# MainBoard_V100_PEAKDET.net
KiCad netlist of a schematic drawn in Altium Designer
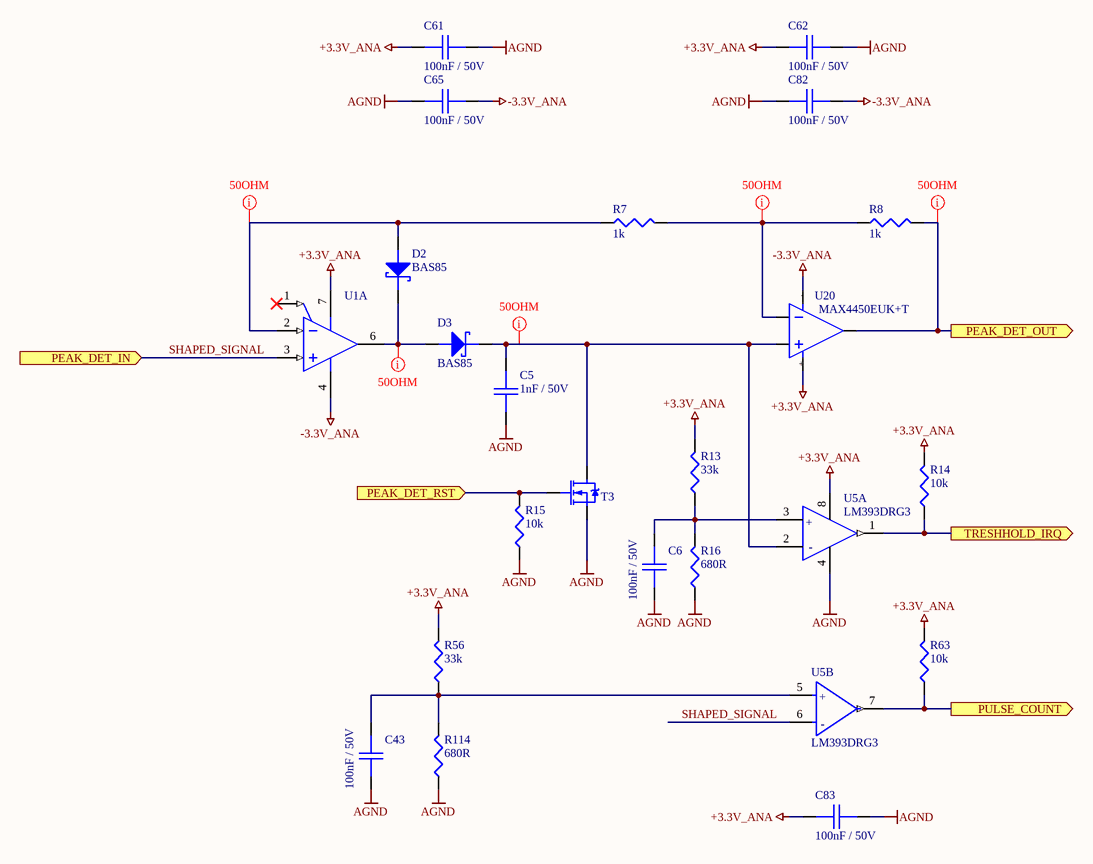
[diagram p0: MainBoard_V100_PEAKDET.SchDoc]

(export (version "E")
  (design (tool "Eeschema 10.0.6"))
  (components
    (comp (ref "C5")
      (value "1nF / 50V")
      (footprint "0805_C")
      (description "1nF 50V X7R")
      (fields (field (name "PART NUMBER") "SMD0805-1nF-50V"))
      (libsource (lib "ALTIUM_DB_LIB") (part "CAP_NONPOL"))
    )
    (comp (ref "C6")
      (value "100nF / 50V")
      (footprint "0805_C")
      (description "100nF 50V X7R")
      (fields (field (name "PART NUMBER") "SMD0805-100nF-50V"))
      (libsource (lib "ALTIUM_DB_LIB") (part "CAP_NONPOL"))
    )
    (comp (ref "C43")
      (value "100nF / 50V")
      (footprint "0805_C")
      (description "100nF 50V X7R")
      (fields (field (name "PART NUMBER") "SMD0805-100nF-50V"))
      (libsource (lib "ALTIUM_DB_LIB") (part "CAP_NONPOL"))
    )
    (comp (ref "C61")
      (value "100nF / 50V")
      (footprint "0805_C")
      (description "100nF 50V X7R")
      (fields (field (name "PART NUMBER") "SMD0805-100nF-50V"))
      (libsource (lib "ALTIUM_DB_LIB") (part "CAP_NONPOL"))
    )
    (comp (ref "C62")
      (value "100nF / 50V")
      (footprint "0805_C")
      (description "100nF 50V X7R")
      (fields (field (name "PART NUMBER") "SMD0805-100nF-50V"))
      (libsource (lib "ALTIUM_DB_LIB") (part "CAP_NONPOL"))
    )
    (comp (ref "C65")
      (value "100nF / 50V")
      (footprint "0805_C")
      (description "100nF 50V X7R")
      (fields (field (name "PART NUMBER") "SMD0805-100nF-50V"))
      (libsource (lib "ALTIUM_DB_LIB") (part "CAP_NONPOL"))
    )
    (comp (ref "C82")
      (value "100nF / 50V")
      (footprint "0805_C")
      (description "100nF 50V X7R")
      (fields (field (name "PART NUMBER") "SMD0805-100nF-50V"))
      (libsource (lib "ALTIUM_DB_LIB") (part "CAP_NONPOL"))
    )
    (comp (ref "C83")
      (value "100nF / 50V")
      (footprint "0805_C")
      (description "100nF 50V X7R")
      (fields (field (name "PART NUMBER") "SMD0805-100nF-50V"))
      (libsource (lib "ALTIUM_DB_LIB") (part "CAP_NONPOL"))
    )
    (comp (ref "D2")
      (value "BAS85")
      (footprint "SOD80")
      (description "Small Signal Schottky Diode, Single, 30 V, 200 mA,  125 °C")
      (libsource (lib "ALTIUM_DB_LIB") (part "DIODE_SCHOTTKY"))
    )
    (comp (ref "D3")
      (value "BAS85")
      (footprint "SOD80")
      (description "Small Signal Schottky Diode, Single, 30 V, 200 mA,  125 °C")
      (libsource (lib "ALTIUM_DB_LIB") (part "DIODE_SCHOTTKY"))
    )
    (comp (ref "R7")
      (value "1k")
      (footprint "0805")
      (description "1k 0805 0.125W 1%")
      (fields (field (name "PART NUMBER") "SMD0805-1k 1%"))
      (libsource (lib "ALTIUM_DB_LIB") (part "RESISTOR"))
    )
    (comp (ref "R8")
      (value "1k")
      (footprint "0805")
      (description "1k 0805 0.125W 1%")
      (fields (field (name "PART NUMBER") "SMD0805-1k 1%"))
      (libsource (lib "ALTIUM_DB_LIB") (part "RESISTOR"))
    )
    (comp (ref "R13")
      (value "33k")
      (footprint "0805")
      (description "33k 0805 0.125W 5%")
      (fields (field (name "PART NUMBER") "SMD0805-33k 5%"))
      (libsource (lib "ALTIUM_DB_LIB") (part "RESISTOR"))
    )
    (comp (ref "R14")
      (value "10k")
      (footprint "0805")
      (description "10k 0805 0.125W 1%")
      (fields (field (name "PART NUMBER") "SMD0805-10k 1%"))
      (libsource (lib "ALTIUM_DB_LIB") (part "RESISTOR"))
    )
    (comp (ref "R15")
      (value "10k")
      (footprint "0805")
      (description "10k 0805 0.125W 1%")
      (fields (field (name "PART NUMBER") "SMD0805-10k 1%"))
      (libsource (lib "ALTIUM_DB_LIB") (part "RESISTOR"))
    )
    (comp (ref "R16")
      (value "680R")
      (footprint "0805")
      (description "680R 0805 0.125W 5%")
      (fields (field (name "PART NUMBER") "SMD0805-680R 5%"))
      (libsource (lib "ALTIUM_DB_LIB") (part "RESISTOR"))
    )
    (comp (ref "R56")
      (value "33k")
      (footprint "0805")
      (description "33k 0805 0.125W 5%")
      (fields (field (name "PART NUMBER") "SMD0805-33k 5%"))
      (libsource (lib "ALTIUM_DB_LIB") (part "RESISTOR"))
    )
    (comp (ref "R63")
      (value "10k")
      (footprint "0805")
      (description "10k 0805 0.125W 1%")
      (fields (field (name "PART NUMBER") "SMD0805-10k 1%"))
      (libsource (lib "ALTIUM_DB_LIB") (part "RESISTOR"))
    )
    (comp (ref "R114")
      (value "680R")
      (footprint "0805")
      (description "680R 0805 0.125W 5%")
      (fields (field (name "PART NUMBER") "SMD0805-680R 5%"))
      (libsource (lib "ALTIUM_DB_LIB") (part "RESISTOR"))
    )
    (comp (ref "T3")
      (value "2N7002K-7")
      (footprint "SOT-23")
      (description "2N7002K-7 Power MOSFET, N Channel, 60 V, 300 mA, 2 ohm, SOT-23, Surface Mount")
      (libsource (lib "ALTIUM_DB_LIB") (part "MOSFET_N_CH"))
    )
    (comp (ref "U1")
      (value "LT1806CS8#PBF")
      (footprint "SO-8")
      (fields
        (field (name "MANUFACTURER") "Linear Technology")
        (field (name "LINEAR TECHNOLOGY PART NUMBER") "LT1806")
      )
      (libsource (lib "ALTIUM_DB_LIB") (part "LT1806CS8#PBF"))
    )
    (comp (ref "U5")
      (value "LM393DRG3")
      (footprint "SO-8")
      (description "IC VOLT COMPARATOR DUAL LP 8SOIC")
      (fields
        (field (name "MANUFACTURER PART NUMBER") "LM393D")
        (field (name "OCTOPART") "https://octopart.com/lm393d-stmicroelectronics-25832")
      )
      (libsource (lib "ALTIUM_DB_LIB") (part "LM393DRG3"))
    )
    (comp (ref "U20")
      (value "MAX4450EUK+T")
      (footprint "SOT-23-5")
      (description "Operational Amplifier, Rail to Rail Output, SOT-23-5, 210 MHz, 485 V/µs")
      (libsource (lib "ALTIUM_DB_LIB") (part "MAX445X"))
    )
  )
  (nets
    (net (code "1") (name "+3.3V_ANA") (class "Default")
      (node (ref "C61") (pin "1") (pintype "passive"))
      (node (ref "C62") (pin "1") (pintype "passive"))
      (node (ref "C83") (pin "1") (pintype "passive"))
      (node (ref "R13") (pin "2") (pintype "passive"))
      (node (ref "R14") (pin "2") (pintype "passive"))
      (node (ref "R56") (pin "2") (pintype "passive"))
      (node (ref "R63") (pin "2") (pintype "passive"))
      (node (ref "U1") (pin "7") (pinfunction "V+_7") (pintype "power_in"))
      (node (ref "U20") (pin "5") (pinfunction "VCC_5") (pintype "passive"))
      (node (ref "U5") (pin "8") (pinfunction "Vcc+_8") (pintype "power_in"))
    )
    (net (code "2") (name "-3.3V_ANA") (class "Default")
      (node (ref "C65") (pin "2") (pintype "passive"))
      (node (ref "C82") (pin "2") (pintype "passive"))
      (node (ref "U1") (pin "4") (pinfunction "V-_4") (pintype "power_in"))
      (node (ref "U20") (pin "4") (pinfunction "GND_4") (pintype "passive"))
    )
    (net (code "3") (name "/PEAK_DET_OUT") (class "Default")
      (node (ref "R8") (pin "2") (pintype "passive"))
      (node (ref "U20") (pin "1") (pinfunction "OUT_1") (pintype "passive"))
    )
    (net (code "4") (name "/PEAK_DET_RST") (class "Default")
      (node (ref "R15") (pin "2") (pintype "passive"))
      (node (ref "T3") (pin "1") (pinfunction "G_1") (pintype "passive"))
    )
    (net (code "5") (name "/PULSE_COUNT") (class "Default")
      (node (ref "R63") (pin "1") (pintype "passive"))
      (node (ref "U5") (pin "7") (pinfunction "Out2_7") (pintype "output"))
    )
    (net (code "6") (name "/SHAPED_SIGNAL") (class "Default")
      (node (ref "U1") (pin "3") (pinfunction "+IN_3") (pintype "input"))
      (node (ref "U5") (pin "6") (pinfunction "In2-_6") (pintype "tri_state"))
    )
    (net (code "7") (name "/TRESHHOLD_IRQ") (class "Default")
      (node (ref "R14") (pin "1") (pintype "passive"))
      (node (ref "U5") (pin "1") (pinfunction "Out1_1") (pintype "output"))
    )
    (net (code "8") (name "AGND") (class "Default")
      (node (ref "C43") (pin "2") (pintype "passive"))
      (node (ref "C5") (pin "2") (pintype "passive"))
      (node (ref "C6") (pin "2") (pintype "passive"))
      (node (ref "C61") (pin "2") (pintype "passive"))
      (node (ref "C62") (pin "2") (pintype "passive"))
      (node (ref "C65") (pin "1") (pintype "passive"))
      (node (ref "C82") (pin "1") (pintype "passive"))
      (node (ref "C83") (pin "2") (pintype "passive"))
      (node (ref "R114") (pin "1") (pintype "passive"))
      (node (ref "R15") (pin "1") (pintype "passive"))
      (node (ref "R16") (pin "1") (pintype "passive"))
      (node (ref "T3") (pin "2") (pinfunction "S_2") (pintype "passive"))
      (node (ref "U5") (pin "4") (pinfunction "Vcc-_4") (pintype "power_in"))
    )
    (net (code "9") (name "Net-(T3-D)") (class "Default")
      (node (ref "C5") (pin "1") (pintype "passive"))
      (node (ref "D3") (pin "K") (pinfunction "K_K") (pintype "passive"))
      (node (ref "T3") (pin "3") (pinfunction "D_3") (pintype "passive"))
      (node (ref "U20") (pin "3") (pinfunction "+_3") (pintype "passive"))
      (node (ref "U5") (pin "2") (pinfunction "In1-_2") (pintype "tri_state"))
    )
    (net (code "10") (name "Net-(U1A--IN)") (class "Default")
      (node (ref "D2") (pin "A") (pinfunction "A_A") (pintype "passive"))
      (node (ref "R7") (pin "1") (pintype "passive"))
      (node (ref "U1") (pin "2") (pinfunction "-IN_2") (pintype "input"))
    )
    (net (code "11") (name "Net-(U1A-OUT)") (class "Default")
      (node (ref "D2") (pin "K") (pinfunction "K_K") (pintype "passive"))
      (node (ref "D3") (pin "A") (pinfunction "A_A") (pintype "passive"))
      (node (ref "U1") (pin "6") (pinfunction "OUT_6") (pintype "tri_state"))
    )
    (net (code "12") (name "Net-(U5A-In1+)") (class "Default")
      (node (ref "C6") (pin "1") (pintype "passive"))
      (node (ref "R13") (pin "1") (pintype "passive"))
      (node (ref "R16") (pin "2") (pintype "passive"))
      (node (ref "U5") (pin "3") (pinfunction "In1+_3") (pintype "tri_state"))
    )
    (net (code "13") (name "Net-(U5B-In2+)") (class "Default")
      (node (ref "C43") (pin "1") (pintype "passive"))
      (node (ref "R114") (pin "2") (pintype "passive"))
      (node (ref "R56") (pin "1") (pintype "passive"))
      (node (ref "U5") (pin "5") (pinfunction "In2+_5") (pintype "tri_state"))
    )
    (net (code "14") (name "Net-(U20--)") (class "Default")
      (node (ref "R7") (pin "2") (pintype "passive"))
      (node (ref "R8") (pin "1") (pintype "passive"))
      (node (ref "U20") (pin "4") (pinfunction "-_4") (pintype "passive"))
    )
    (net (code "15") (name "unconnected-(U1A-~{SHDN}-Pad1)") (class "Default")
      (node (ref "U1") (pin "1") (pinfunction "~{SHDN}_1") (pintype "input+no_connect"))
    )
  )
)
